# plugV15-pth.net
KiCad netlist of a schematic drawn in EAGLE
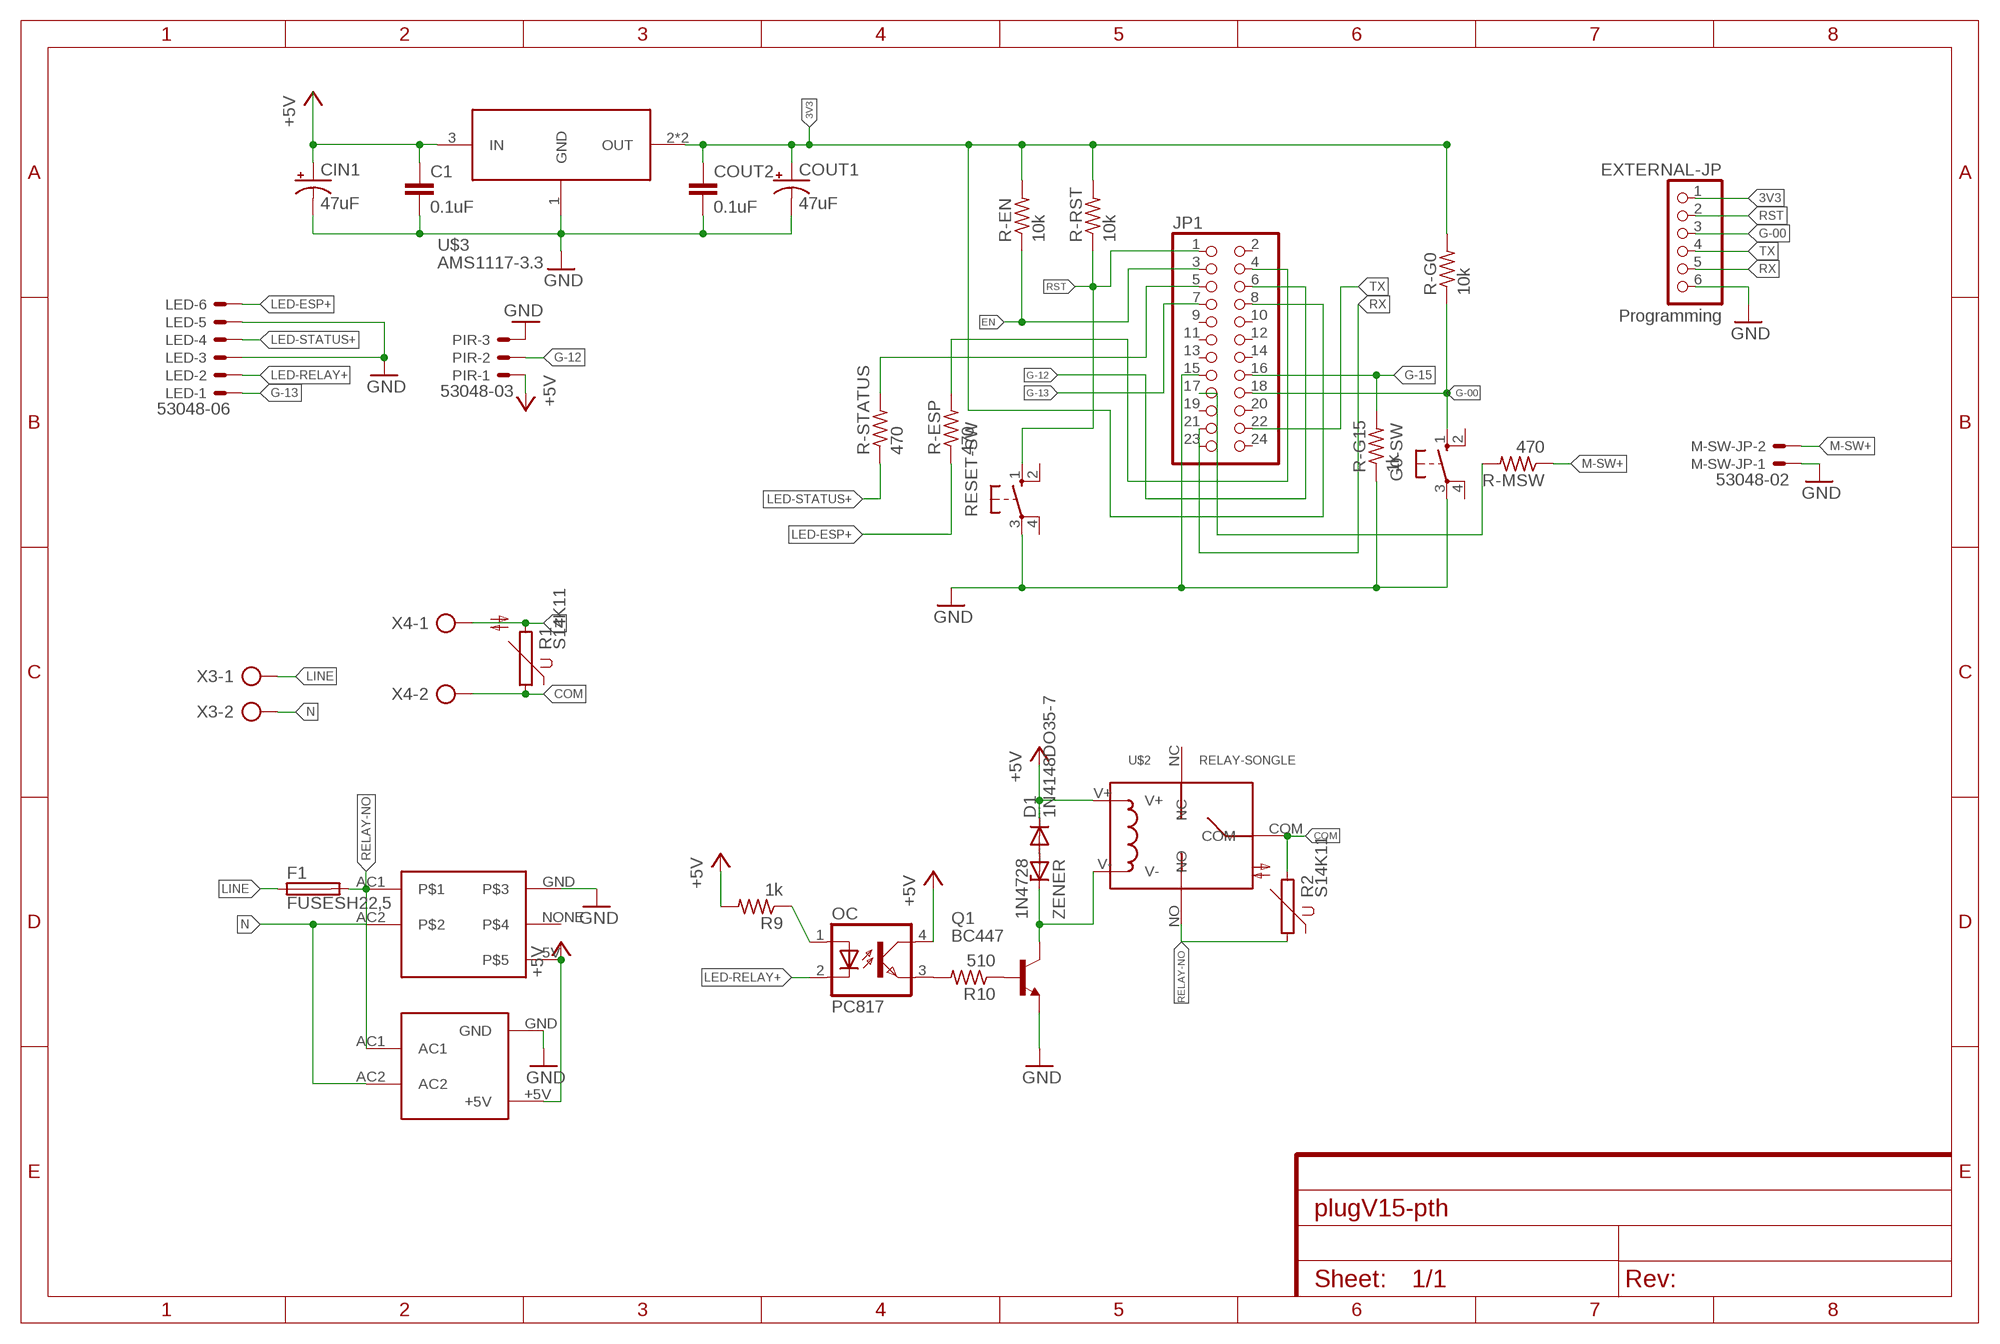
[diagram p0: schematic, sheet 1]

(export (version "E")
  (design (tool "Eeschema 10.0.6"))
  (components
    (comp (ref "C1")
      (value "0.1uF")
      (footprint "eagle-import:C050-024X044")
      (libsource (lib "eagle-import") (part "C-EU050-024X044"))
    )
    (comp (ref "CIN1")
      (value "47uF")
      (footprint "eagle-import:E2,5-5")
      (libsource (lib "eagle-import") (part "CPOL-USE2.5-5"))
    )
    (comp (ref "COUT1")
      (value "47uF")
      (footprint "eagle-import:E2,5-5")
      (libsource (lib "eagle-import") (part "CPOL-USE2.5-5"))
    )
    (comp (ref "COUT2")
      (value "0.1uF")
      (footprint "eagle-import:C050-024X044")
      (libsource (lib "eagle-import") (part "C-EU050-024X044"))
    )
    (comp (ref "D1")
      (value "1N4148DO35-7")
      (footprint "eagle-import:DO35-7")
      (libsource (lib "eagle-import") (part "1N4148DO35-7"))
    )
    (comp (ref "EXTERNAL-JP")
      (value "Programming")
      (footprint "eagle-import:1X06")
      (libsource (lib "eagle-import") (part "PINHD-1X6"))
    )
    (comp (ref "F1")
      (value "FUSESH22,5")
      (footprint "eagle-import:SH22,5")
      (libsource (lib "eagle-import") (part "FUSESH22,5"))
    )
    (comp (ref "G0-SW")
      (value "10-XX")
      (footprint "eagle-import:B3F-10XX")
      (fields (field (name "MPN") "B3F-1000"))
      (libsource (lib "eagle-import") (part "10-XX"))
    )
    (comp (ref "JP1")
      (value "PINHD-2X12")
      (footprint "eagle-import:2X12")
      (libsource (lib "eagle-import") (part "PINHD-2X12"))
    )
    (comp (ref "LED")
      (value "53048-06")
      (footprint "eagle-import:53048-06")
      (fields (field (name "MF") "WALDOM/MOLEX") (field (name "MPN") "53048-0610"))
      (libsource (lib "eagle-import") (part "53?-06048"))
    )
    (comp (ref "M-SW-JP")
      (value "53048-02")
      (footprint "eagle-import:53048-02")
      (fields (field (name "MF") "MOLEX") (field (name "MPN") "53048-0210"))
      (libsource (lib "eagle-import") (part "53?-02048"))
    )
    (comp (ref "OC")
      (value "PC817")
      (footprint "eagle-import:DIL04")
      (fields (field (name "MPN") "PC817X4J000F"))
      (libsource (lib "eagle-import") (part "PC817"))
    )
    (comp (ref "PIR")
      (value "53048-03")
      (footprint "eagle-import:53048-03")
      (fields (field (name "MF") "WALDOM/MOLEX") (field (name "MPN") "53048-0310"))
      (libsource (lib "eagle-import") (part "53?-03048"))
    )
    (comp (ref "Q1")
      (value "BC447")
      (footprint "eagle-import:TO92-EBC")
      (libsource (lib "eagle-import") (part "BC447"))
    )
    (comp (ref "R-EN")
      (value "10k")
      (footprint "eagle-import:0207_10")
      (libsource (lib "eagle-import") (part "R-US_0207/10"))
    )
    (comp (ref "R-ESP")
      (value "470")
      (footprint "eagle-import:0207_10")
      (libsource (lib "eagle-import") (part "R-US_0207/10"))
    )
    (comp (ref "R-G0")
      (value "10k")
      (footprint "eagle-import:0207_10")
      (libsource (lib "eagle-import") (part "R-US_0207/10"))
    )
    (comp (ref "R-G15")
      (value "1k")
      (footprint "eagle-import:0207_10")
      (libsource (lib "eagle-import") (part "R-US_0207/10"))
    )
    (comp (ref "R-MSW")
      (value "470")
      (footprint "eagle-import:0207_10")
      (libsource (lib "eagle-import") (part "R-US_0207/10"))
    )
    (comp (ref "R-RST")
      (value "10k")
      (footprint "eagle-import:0207_10")
      (libsource (lib "eagle-import") (part "R-US_0207/10"))
    )
    (comp (ref "R-STATUS")
      (value "470")
      (footprint "eagle-import:0207_10")
      (libsource (lib "eagle-import") (part "R-US_0207/10"))
    )
    (comp (ref "R1")
      (value "S14K11")
      (footprint "eagle-import:S14K11")
      (libsource (lib "eagle-import") (part "S14K11"))
    )
    (comp (ref "R2")
      (value "S14K11")
      (footprint "eagle-import:S14K11")
      (libsource (lib "eagle-import") (part "S14K11"))
    )
    (comp (ref "R9")
      (value "1k")
      (footprint "eagle-import:0207_10")
      (libsource (lib "eagle-import") (part "R-US_0207/10"))
    )
    (comp (ref "R10")
      (value "510")
      (footprint "eagle-import:0207_10")
      (libsource (lib "eagle-import") (part "R-US_0207/10"))
    )
    (comp (ref "RESET-SW")
      (value "10-XX")
      (footprint "eagle-import:B3F-10XX")
      (fields (field (name "MPN") "B3F-1000"))
      (libsource (lib "eagle-import") (part "10-XX"))
    )
    (comp (ref "U$1")
      (value "HLK-PM01")
      (footprint "eagle-import:HLK-PM01")
      (libsource (lib "eagle-import") (part "HLK-PM01"))
    )
    (comp (ref "U$2")
      (value "RELAY-SONGLE")
      (footprint "eagle-import:RELAY-SONGLE")
      (libsource (lib "eagle-import") (part "RELAY-SONGLE"))
    )
    (comp (ref "U$3")
      (value "AMS1117-3.3")
      (footprint "eagle-import:SOT-223")
      (libsource (lib "eagle-import") (part "AMS1117-3.3"))
    )
    (comp (ref "U$4")
      (value "POWERSUPPLY-5V-700MA")
      (footprint "eagle-import:POWERSUPPLY-5V-700MA")
      (libsource (lib "eagle-import") (part "POWERSUPPLY-5V-700MA"))
    )
    (comp (ref "X3")
      (value "AK300/2")
      (footprint "eagle-import:AK300_2")
      (libsource (lib "eagle-import") (part "AK300/2"))
    )
    (comp (ref "X4")
      (value "AK300/2")
      (footprint "eagle-import:AK300_2")
      (libsource (lib "eagle-import") (part "AK300/2"))
    )
    (comp (ref "ZENER")
      (value "1N4728")
      (footprint "eagle-import:DO41Z10")
      (libsource (lib "eagle-import") (part "1N4728"))
    )
  )
  (nets
    (net (code "1") (name "+5V") (class "Default")
      (node (ref "C1") (pin "1") (pinfunction "1_1") (pintype "passive"))
      (node (ref "CIN1") (pin "+") (pinfunction "+_+") (pintype "passive"))
      (node (ref "D1") (pin "C") (pinfunction "C_C") (pintype "passive"))
      (node (ref "OC") (pin "4") (pinfunction "COL_4") (pintype "passive"))
      (node (ref "PIR") (pin "1") (pinfunction "S_1") (pintype "passive"))
      (node (ref "R9") (pin "2") (pinfunction "2_2") (pintype "passive"))
      (node (ref "U$1") (pin "+5V") (pinfunction "+5V_+5V") (pintype "bidirectional"))
      (node (ref "U$2") (pin "V+") (pinfunction "V+_V+") (pintype "bidirectional"))
      (node (ref "U$3") (pin "3") (pinfunction "IN_3") (pintype "input"))
      (node (ref "U$4") (pin "5V") (pinfunction "P$5_5V") (pintype "bidirectional"))
    )
    (net (code "2") (name "3V3") (class "Default")
      (node (ref "COUT1") (pin "+") (pinfunction "+_+") (pintype "passive"))
      (node (ref "COUT2") (pin "1") (pinfunction "1_1") (pintype "passive"))
      (node (ref "EXTERNAL-JP") (pin "1") (pinfunction "1_1") (pintype "passive"))
      (node (ref "JP1") (pin "8") (pinfunction "8_8") (pintype "passive"))
      (node (ref "R-EN") (pin "2") (pinfunction "2_2") (pintype "passive"))
      (node (ref "R-G0") (pin "2") (pinfunction "2_2") (pintype "passive"))
      (node (ref "R-RST") (pin "2") (pinfunction "2_2") (pintype "passive"))
      (node (ref "U$3") (pin "2") (pinfunction "OUT_2") (pintype "output"))
      (node (ref "U$3") (pin "4") (pinfunction "OUT_4") (pintype "output"))
    )
    (net (code "3") (name "COM") (class "Default")
      (node (ref "R1") (pin "1") (pinfunction "1_1") (pintype "passive"))
      (node (ref "R2") (pin "2") (pinfunction "2_2") (pintype "passive"))
      (node (ref "U$2") (pin "COM") (pinfunction "COM_COM") (pintype "bidirectional"))
      (node (ref "X4") (pin "2") (pinfunction "KL_2") (pintype "passive"))
    )
    (net (code "4") (name "EN") (class "Default")
      (node (ref "JP1") (pin "3") (pinfunction "3_3") (pintype "passive"))
      (node (ref "R-EN") (pin "1") (pinfunction "1_1") (pintype "passive"))
    )
    (net (code "5") (name "G-00") (class "Default")
      (node (ref "EXTERNAL-JP") (pin "3") (pinfunction "3_3") (pintype "passive"))
      (node (ref "G0-SW") (pin "1") (pinfunction "S_1") (pintype "passive"))
      (node (ref "JP1") (pin "18") (pinfunction "18_18") (pintype "passive"))
      (node (ref "R-G0") (pin "1") (pinfunction "1_1") (pintype "passive"))
    )
    (net (code "6") (name "G-12") (class "Default")
      (node (ref "JP1") (pin "6") (pinfunction "6_6") (pintype "passive"))
      (node (ref "PIR") (pin "2") (pinfunction "S_2") (pintype "passive"))
    )
    (net (code "7") (name "G-13") (class "Default")
      (node (ref "JP1") (pin "7") (pinfunction "7_7") (pintype "passive"))
      (node (ref "LED") (pin "1") (pinfunction "S_1") (pintype "passive"))
    )
    (net (code "8") (name "G-15") (class "Default")
      (node (ref "JP1") (pin "16") (pinfunction "16_16") (pintype "passive"))
      (node (ref "R-G15") (pin "2") (pinfunction "2_2") (pintype "passive"))
    )
    (net (code "9") (name "GND") (class "Default")
      (node (ref "C1") (pin "2") (pinfunction "2_2") (pintype "passive"))
      (node (ref "CIN1") (pin "-") (pinfunction "-_-") (pintype "passive"))
      (node (ref "COUT1") (pin "-") (pinfunction "-_-") (pintype "passive"))
      (node (ref "COUT2") (pin "2") (pinfunction "2_2") (pintype "passive"))
      (node (ref "EXTERNAL-JP") (pin "6") (pinfunction "6_6") (pintype "passive"))
      (node (ref "G0-SW") (pin "3") (pinfunction "P_3") (pintype "passive"))
      (node (ref "JP1") (pin "15") (pinfunction "15_15") (pintype "passive"))
      (node (ref "LED") (pin "3") (pinfunction "S_3") (pintype "passive"))
      (node (ref "LED") (pin "5") (pinfunction "S_5") (pintype "passive"))
      (node (ref "M-SW-JP") (pin "1") (pinfunction "S_1") (pintype "passive"))
      (node (ref "PIR") (pin "3") (pinfunction "S_3") (pintype "passive"))
      (node (ref "Q1") (pin "E") (pinfunction "E_E") (pintype "passive"))
      (node (ref "R-G15") (pin "1") (pinfunction "1_1") (pintype "passive"))
      (node (ref "RESET-SW") (pin "3") (pinfunction "P_3") (pintype "passive"))
      (node (ref "U$1") (pin "GND") (pinfunction "GND_GND") (pintype "bidirectional"))
      (node (ref "U$3") (pin "1") (pinfunction "GND_1") (pintype "passive"))
      (node (ref "U$4") (pin "GND") (pinfunction "P$3_GND") (pintype "bidirectional"))
    )
    (net (code "10") (name "LED-ESP+") (class "Default")
      (node (ref "LED") (pin "6") (pinfunction "S_6") (pintype "passive"))
      (node (ref "R-ESP") (pin "1") (pinfunction "1_1") (pintype "passive"))
    )
    (net (code "11") (name "LED-RELAY+") (class "Default")
      (node (ref "LED") (pin "2") (pinfunction "S_2") (pintype "passive"))
      (node (ref "OC") (pin "2") (pinfunction "C_2") (pintype "passive"))
    )
    (net (code "12") (name "LED-STATUS+") (class "Default")
      (node (ref "LED") (pin "4") (pinfunction "S_4") (pintype "passive"))
      (node (ref "R-STATUS") (pin "1") (pinfunction "1_1") (pintype "passive"))
    )
    (net (code "13") (name "LINE") (class "Default")
      (node (ref "F1") (pin "1") (pinfunction "1_1") (pintype "passive"))
      (node (ref "X3") (pin "1") (pinfunction "KL_1") (pintype "passive"))
    )
    (net (code "14") (name "M-SW+") (class "Default")
      (node (ref "M-SW-JP") (pin "2") (pinfunction "S_2") (pintype "passive"))
      (node (ref "R-MSW") (pin "1") (pinfunction "1_1") (pintype "passive"))
    )
    (net (code "15") (name "N") (class "Default")
      (node (ref "R1") (pin "2") (pinfunction "2_2") (pintype "passive"))
      (node (ref "U$1") (pin "AC2") (pinfunction "AC2_AC2") (pintype "bidirectional"))
      (node (ref "U$4") (pin "AC2") (pinfunction "P$2_AC2") (pintype "bidirectional"))
      (node (ref "X3") (pin "2") (pinfunction "KL_2") (pintype "passive"))
      (node (ref "X4") (pin "1") (pinfunction "KL_1") (pintype "passive"))
    )
    (net (code "16") (name "Net-(D1-PadA)") (class "Default")
      (node (ref "D1") (pin "A") (pinfunction "A_A") (pintype "passive"))
      (node (ref "ZENER") (pin "A") (pinfunction "A_A") (pintype "passive"))
    )
    (net (code "17") (name "Net-(JP1-Pad4)") (class "Default")
      (node (ref "JP1") (pin "4") (pinfunction "4_4") (pintype "passive"))
      (node (ref "R-ESP") (pin "2") (pinfunction "2_2") (pintype "passive"))
    )
    (net (code "18") (name "Net-(JP1-Pad5)") (class "Default")
      (node (ref "JP1") (pin "5") (pinfunction "5_5") (pintype "passive"))
      (node (ref "R-STATUS") (pin "2") (pinfunction "2_2") (pintype "passive"))
    )
    (net (code "19") (name "Net-(JP1-Pad17)") (class "Default")
      (node (ref "JP1") (pin "17") (pinfunction "17_17") (pintype "passive"))
      (node (ref "R-MSW") (pin "2") (pinfunction "2_2") (pintype "passive"))
    )
    (net (code "20") (name "Net-(OC-A)") (class "Default")
      (node (ref "OC") (pin "1") (pinfunction "A_1") (pintype "passive"))
      (node (ref "R9") (pin "1") (pinfunction "1_1") (pintype "passive"))
    )
    (net (code "21") (name "Net-(OC-EMIT)") (class "Default")
      (node (ref "OC") (pin "3") (pinfunction "EMIT_3") (pintype "passive"))
      (node (ref "R10") (pin "2") (pinfunction "2_2") (pintype "passive"))
    )
    (net (code "22") (name "Net-(Q1-PadB)") (class "Default")
      (node (ref "Q1") (pin "B") (pinfunction "B_B") (pintype "passive"))
      (node (ref "R10") (pin "1") (pinfunction "1_1") (pintype "passive"))
    )
    (net (code "23") (name "Net-(Q1-PadC)") (class "Default")
      (node (ref "Q1") (pin "C") (pinfunction "C_C") (pintype "passive"))
      (node (ref "U$2") (pin "V-") (pinfunction "V-_V-") (pintype "bidirectional"))
      (node (ref "ZENER") (pin "C") (pinfunction "C_C") (pintype "passive"))
    )
    (net (code "24") (name "RELAY-NO") (class "Default")
      (node (ref "F1") (pin "2") (pinfunction "2_2") (pintype "passive"))
      (node (ref "R2") (pin "1") (pinfunction "1_1") (pintype "passive"))
      (node (ref "U$1") (pin "AC1") (pinfunction "AC1_AC1") (pintype "bidirectional"))
      (node (ref "U$2") (pin "NO") (pinfunction "NO_NO") (pintype "bidirectional"))
      (node (ref "U$4") (pin "AC1") (pinfunction "P$1_AC1") (pintype "bidirectional"))
    )
    (net (code "25") (name "RST") (class "Default")
      (node (ref "EXTERNAL-JP") (pin "2") (pinfunction "2_2") (pintype "passive"))
      (node (ref "JP1") (pin "1") (pinfunction "1_1") (pintype "passive"))
      (node (ref "R-RST") (pin "1") (pinfunction "1_1") (pintype "passive"))
      (node (ref "RESET-SW") (pin "1") (pinfunction "S_1") (pintype "passive"))
    )
    (net (code "26") (name "RX") (class "Default")
      (node (ref "EXTERNAL-JP") (pin "5") (pinfunction "5_5") (pintype "passive"))
      (node (ref "JP1") (pin "21") (pinfunction "21_21") (pintype "passive"))
    )
    (net (code "27") (name "TX") (class "Default")
      (node (ref "EXTERNAL-JP") (pin "4") (pinfunction "4_4") (pintype "passive"))
      (node (ref "JP1") (pin "22") (pinfunction "22_22") (pintype "passive"))
    )
    (net (code "28") (name "unconnected-(G0-SW-P1-Pad4)") (class "Default")
      (node (ref "G0-SW") (pin "4") (pinfunction "P1_4") (pintype "passive"))
    )
    (net (code "29") (name "unconnected-(G0-SW-S1-Pad2)") (class "Default")
      (node (ref "G0-SW") (pin "2") (pinfunction "S1_2") (pintype "passive"))
    )
    (net (code "30") (name "unconnected-(JP1-Pad2)") (class "Default")
      (node (ref "JP1") (pin "2") (pinfunction "2_2") (pintype "passive"))
    )
    (net (code "31") (name "unconnected-(JP1-Pad9)") (class "Default")
      (node (ref "JP1") (pin "9") (pinfunction "9_9") (pintype "passive"))
    )
    (net (code "32") (name "unconnected-(JP1-Pad10)") (class "Default")
      (node (ref "JP1") (pin "10") (pinfunction "10_10") (pintype "passive"))
    )
    (net (code "33") (name "unconnected-(JP1-Pad11)") (class "Default")
      (node (ref "JP1") (pin "11") (pinfunction "11_11") (pintype "passive"))
    )
    (net (code "34") (name "unconnected-(JP1-Pad12)") (class "Default")
      (node (ref "JP1") (pin "12") (pinfunction "12_12") (pintype "passive"))
    )
    (net (code "35") (name "unconnected-(JP1-Pad13)") (class "Default")
      (node (ref "JP1") (pin "13") (pinfunction "13_13") (pintype "passive"))
    )
    (net (code "36") (name "unconnected-(JP1-Pad14)") (class "Default")
      (node (ref "JP1") (pin "14") (pinfunction "14_14") (pintype "passive"))
    )
    (net (code "37") (name "unconnected-(JP1-Pad19)") (class "Default")
      (node (ref "JP1") (pin "19") (pinfunction "19_19") (pintype "passive"))
    )
    (net (code "38") (name "unconnected-(JP1-Pad20)") (class "Default")
      (node (ref "JP1") (pin "20") (pinfunction "20_20") (pintype "passive"))
    )
    (net (code "39") (name "unconnected-(JP1-Pad23)") (class "Default")
      (node (ref "JP1") (pin "23") (pinfunction "23_23") (pintype "passive"))
    )
    (net (code "40") (name "unconnected-(JP1-Pad24)") (class "Default")
      (node (ref "JP1") (pin "24") (pinfunction "24_24") (pintype "passive"))
    )
    (net (code "41") (name "unconnected-(RESET-SW-P1-Pad4)") (class "Default")
      (node (ref "RESET-SW") (pin "4") (pinfunction "P1_4") (pintype "passive"))
    )
    (net (code "42") (name "unconnected-(RESET-SW-S1-Pad2)") (class "Default")
      (node (ref "RESET-SW") (pin "2") (pinfunction "S1_2") (pintype "passive"))
    )
    (net (code "43") (name "unconnected-(U$2-PadNC)") (class "Default")
      (node (ref "U$2") (pin "NC") (pinfunction "NC_NC") (pintype "bidirectional"))
    )
    (net (code "44") (name "unconnected-(U$4-P$4-PadNONE)") (class "Default")
      (node (ref "U$4") (pin "NONE") (pinfunction "P$4_NONE") (pintype "bidirectional"))
    )
  )
)
